# Main.net
KiCad netlist of a schematic drawn in Altium Designer
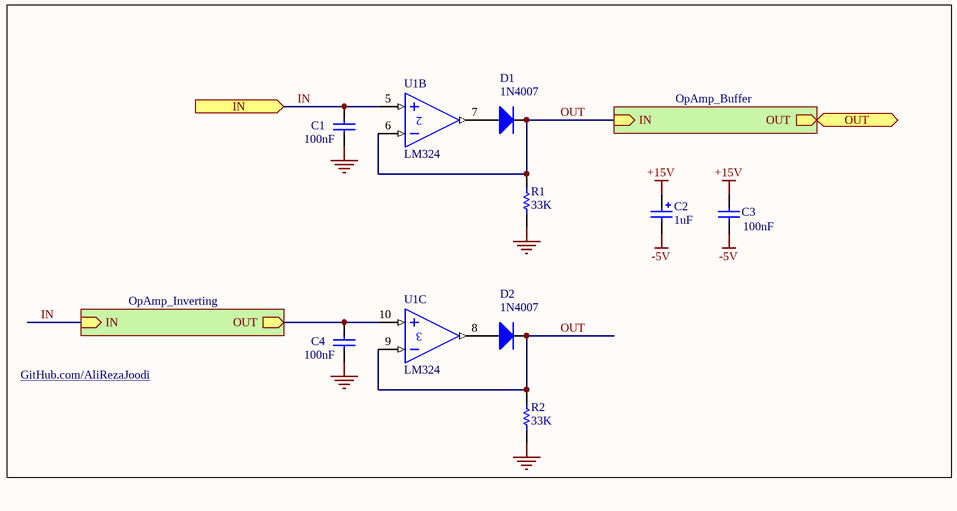
[diagram p0: Main.SchDoc]

(export (version "E")
  (design (tool "Eeschema 10.0.6"))
  (components
    (comp (ref "C1")
      (value "100nF")
      (footprint "0805")
      (description "Capacitor")
      (fields
        (field (name "MANUFACTURER") "Generic Components")
        (field (name "Comment") "C?")
        (field (name "PUBLISHER") "Altium Limited")
      )
      (libsource (lib "Miscellaneous Devices") (part "Cap"))
    )
    (comp (ref "C2")
      (value "1uF")
      (footprint "Cap_B")
      (description "Polarized Capacitor (Radial)")
      (fields
        (field (name "MANUFACTURER") "Generic Components")
        (field (name "Comment") "Capacitor")
        (field (name "PUBLISHER") "Altium Limited")
      )
      (libsource (lib "Miscellaneous Devices") (part "Cap Pol1"))
    )
    (comp (ref "C3")
      (value "100nF")
      (footprint "0805")
      (description "Capacitor")
      (fields (field (name "Comment") "Cap") (field (name "PUBLISHER") "Altium Limited"))
      (libsource (lib "Miscellaneous Devices") (part "Cap"))
    )
    (comp (ref "C4")
      (value "100nF")
      (footprint "0805")
      (description "Capacitor")
      (fields
        (field (name "MANUFACTURER") "Generic Components")
        (field (name "Comment") "C?")
        (field (name "PUBLISHER") "Altium Limited")
      )
      (libsource (lib "Miscellaneous Devices") (part "Cap"))
    )
    (comp (ref "D1")
      (value "1N4007")
      (footprint "MELF-D3516-1406")
      (description "Default Diode")
      (fields (field (name "MANUFACTURER") "Generic Components") (field (name "PUBLISHER") "Altium Limited"))
      (libsource (lib "Miscellaneous Devices") (part "Diode"))
    )
    (comp (ref "D2")
      (value "1N4007")
      (footprint "MELF-D3516-1406")
      (description "Default Diode")
      (fields (field (name "MANUFACTURER") "Generic Components") (field (name "PUBLISHER") "Altium Limited"))
      (libsource (lib "Miscellaneous Devices") (part "Diode"))
    )
    (comp (ref "R1")
      (value "33K")
      (footprint "0805")
      (description "Resistor")
      (fields (field (name "Comment") "Res1") (field (name "PUBLISHER") "Altium Limited"))
      (libsource (lib "Miscellaneous Devices") (part "Res1"))
    )
    (comp (ref "R2")
      (value "33K")
      (footprint "0805")
      (description "Resistor")
      (fields (field (name "Comment") "Res1") (field (name "PUBLISHER") "Altium Limited"))
      (libsource (lib "Miscellaneous Devices") (part "Res1"))
    )
    (comp (ref "U1")
      (value "LM324")
      (footprint "SOP127P636-14N")
      (description "Quad Low-Power Operational Amplifier")
      (fields (field (name "PUBLISHER") "Altium Limited"))
      (libsource (lib "my Libraries") (part "LM324"))
    )
  )
  (nets
    (net (code "1") (name "+15V") (class "Default")
      (node (ref "C2") (pin "1") (pinfunction "1_1") (pintype "passive"))
      (node (ref "C3") (pin "1") (pinfunction "1_1") (pintype "passive"))
    )
    (net (code "2") (name "-5V") (class "Default")
      (node (ref "C2") (pin "2") (pinfunction "2_2") (pintype "passive"))
      (node (ref "C3") (pin "2") (pinfunction "2_2") (pintype "passive"))
    )
    (net (code "3") (name "/IN") (class "Default")
      (node (ref "C1") (pin "1") (pinfunction "1_1") (pintype "passive"))
      (node (ref "U1") (pin "5") (pinfunction "IN+_5") (pintype "input"))
    )
    (net (code "4") (name "/OUT") (class "Default")
      (node (ref "D1") (pin "2") (pinfunction "K_2") (pintype "passive"))
      (node (ref "D2") (pin "2") (pinfunction "K_2") (pintype "passive"))
      (node (ref "R1") (pin "2") (pinfunction "2_2") (pintype "passive"))
      (node (ref "R2") (pin "2") (pinfunction "2_2") (pintype "passive"))
      (node (ref "U1") (pin "6") (pinfunction "IN-_6") (pintype "input"))
      (node (ref "U1") (pin "9") (pinfunction "IN-_9") (pintype "input"))
    )
    (net (code "5") (name "/OUT_1") (class "Default")
      (node (ref "C4") (pin "1") (pinfunction "1_1") (pintype "passive"))
      (node (ref "U1") (pin "10") (pinfunction "IN+_10") (pintype "input"))
    )
    (net (code "6") (name "GND") (class "Default")
      (node (ref "C1") (pin "2") (pinfunction "2_2") (pintype "passive"))
      (node (ref "C4") (pin "2") (pinfunction "2_2") (pintype "passive"))
      (node (ref "R1") (pin "1") (pinfunction "1_1") (pintype "passive"))
      (node (ref "R2") (pin "1") (pinfunction "1_1") (pintype "passive"))
    )
    (net (code "7") (name "Net-(D1-A)") (class "Default")
      (node (ref "D1") (pin "1") (pinfunction "A_1") (pintype "passive"))
      (node (ref "U1") (pin "7") (pinfunction "OUT_7") (pintype "output"))
    )
    (net (code "8") (name "Net-(D2-A)") (class "Default")
      (node (ref "D2") (pin "1") (pinfunction "A_1") (pintype "passive"))
      (node (ref "U1") (pin "8") (pinfunction "OUT_8") (pintype "output"))
    )
  )
)
